# ESP32.net
KiCad netlist of a schematic drawn in Altium Designer
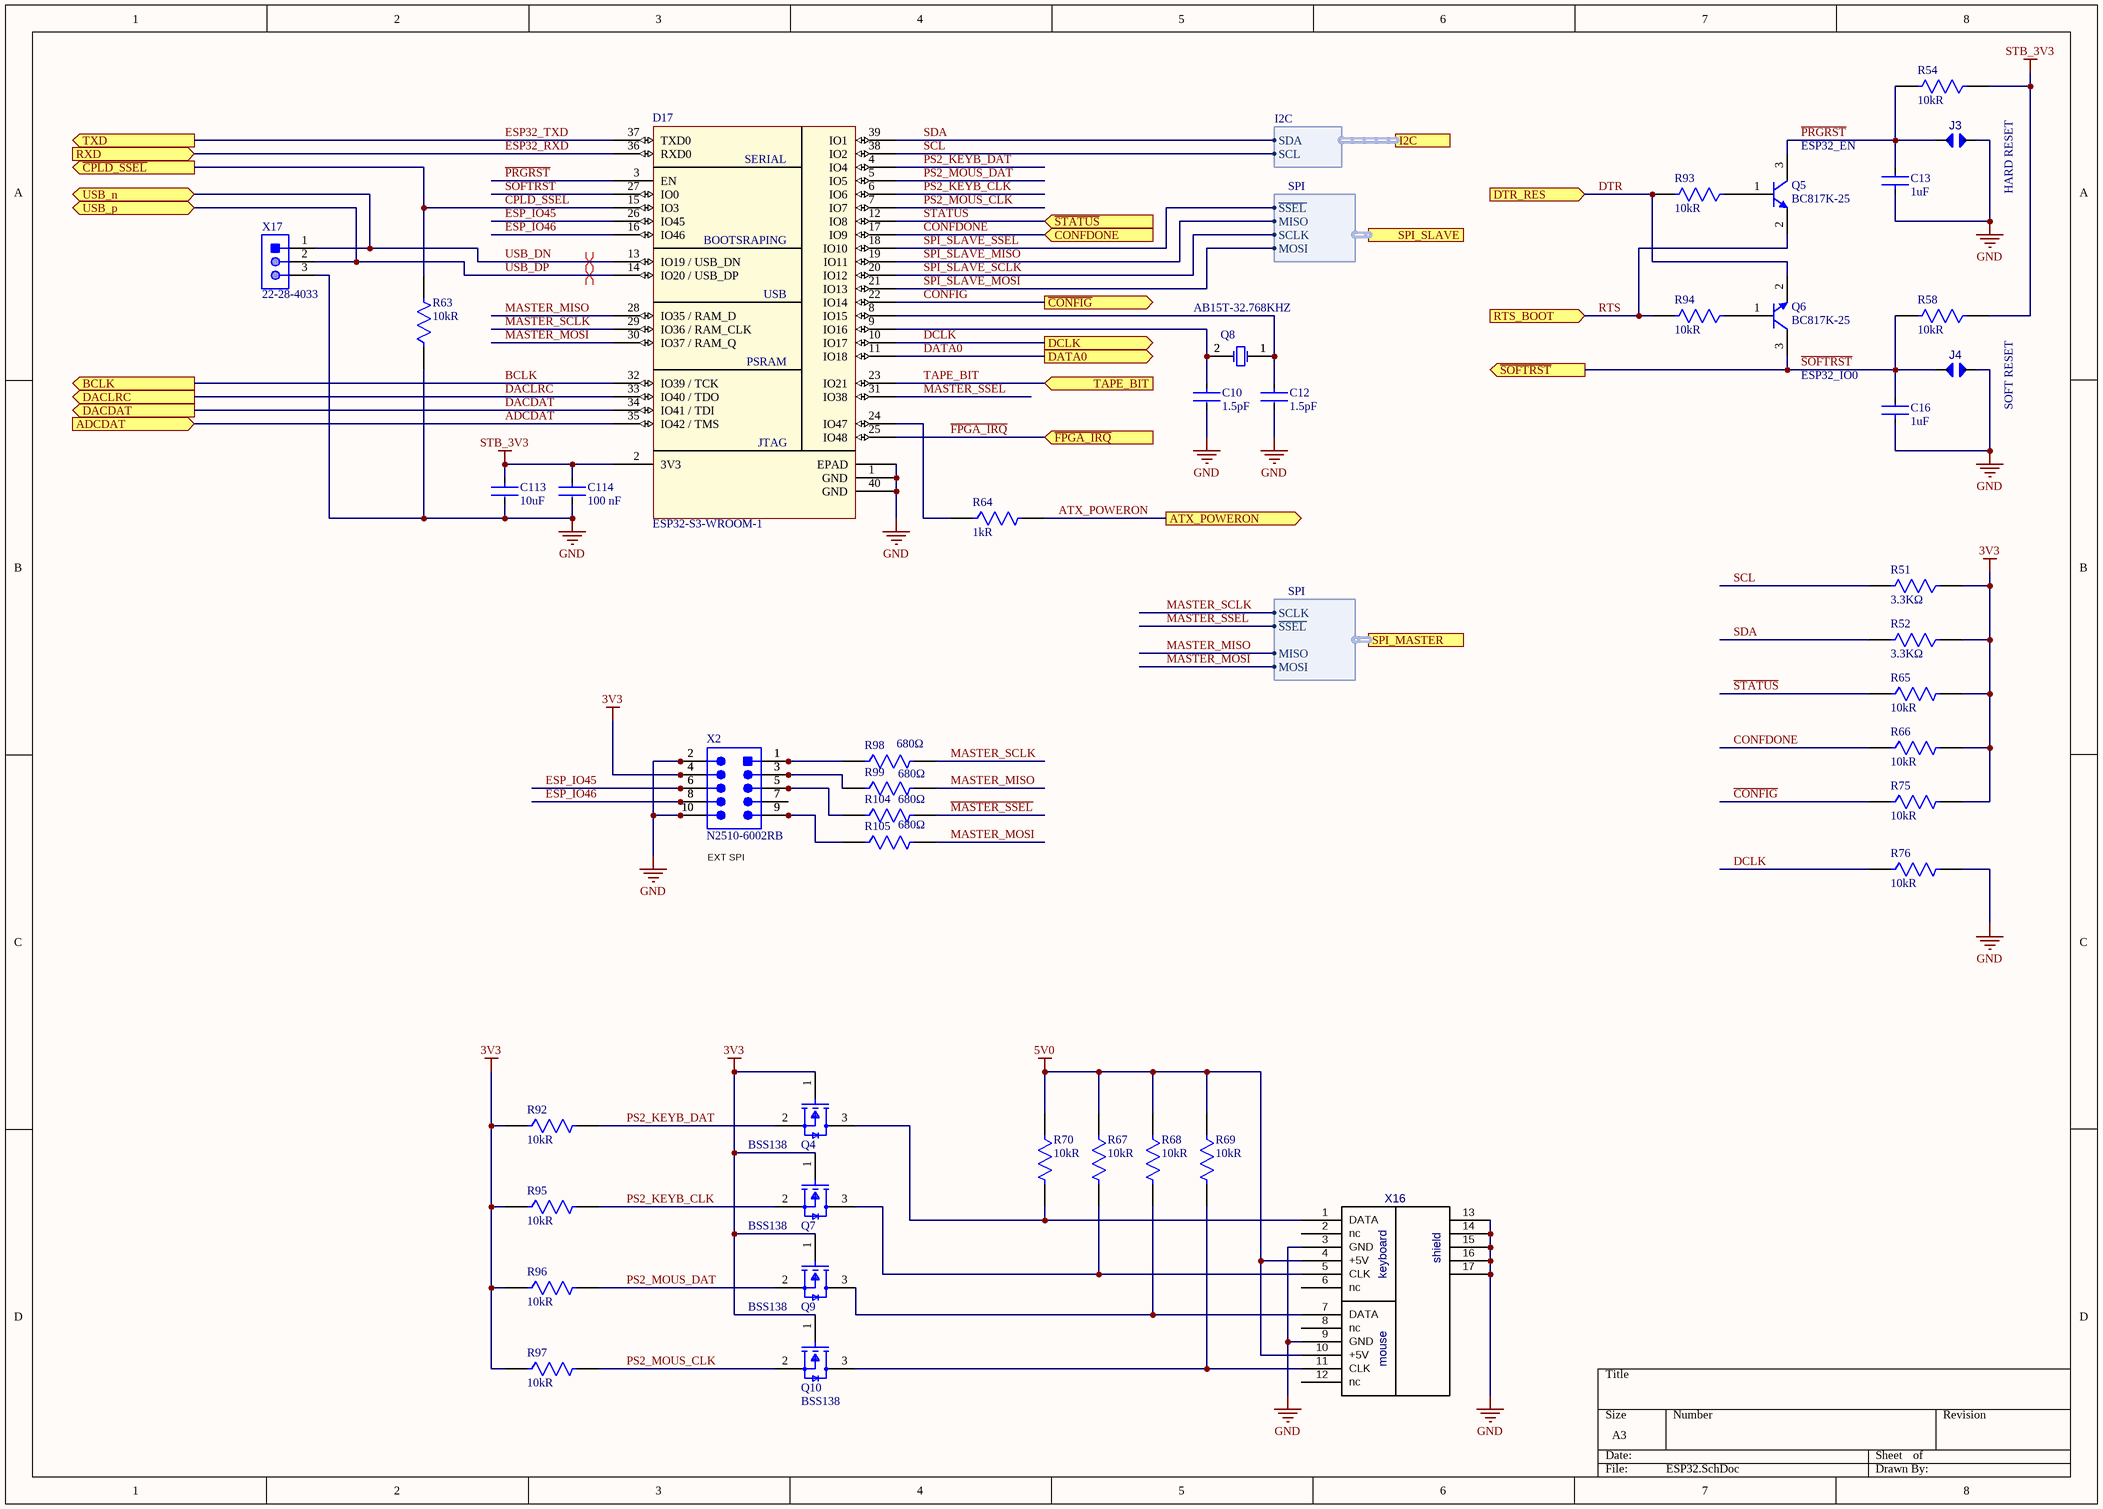
[diagram p0: ESP32.SchDoc]

(export (version "E")
  (design (tool "Eeschema 10.0.6"))
  (components
    (comp (ref "C10")
      (value "CL21C1R5CBANNNC")
      (footprint "FP-CL21-IPC_A")
      (description "CL21 Series 0805 1.5pF 50V ±0.25pF Tolerance C0G Multilayer Ceramic Chip Capacitor")
      (fields (field (name "CAPACITANCE") "1.5pF") (field (name "MANUFACTURER") "Samsung"))
      (libsource (lib "SchLib") (part "CMP-13271-001925-1"))
    )
    (comp (ref "C12")
      (value "CL21C1R5CBANNNC")
      (footprint "FP-CL21-IPC_A")
      (description "CL21 Series 0805 1.5pF 50V ±0.25pF Tolerance C0G Multilayer Ceramic Chip Capacitor")
      (fields (field (name "CAPACITANCE") "1.5pF") (field (name "MANUFACTURER") "Samsung"))
      (libsource (lib "SchLib") (part "CMP-13271-001925-1"))
    )
    (comp (ref "C13")
      (value "GCM21BR71E105KA56L")
      (footprint "FP-GCM21B-0_15-IPC_A")
      (description "Ceramic Capacitor for Automotive 1uF ±10% 25VDC X7R 0805 Embossed T/R")
      (fields (field (name "CAPACITANCE") "1uF") (field (name "MANUFACTURER") "Murata"))
      (libsource (lib "SchLib") (part "CMP-2007-03346-2"))
    )
    (comp (ref "C16")
      (value "GCM21BR71E105KA56L")
      (footprint "FP-GCM21B-0_15-IPC_A")
      (description "Ceramic Capacitor for Automotive 1uF ±10% 25VDC X7R 0805 Embossed T/R")
      (fields (field (name "CAPACITANCE") "1uF") (field (name "MANUFACTURER") "Murata"))
      (libsource (lib "SchLib") (part "CMP-2007-03346-2"))
    )
    (comp (ref "C113")
      (value "C0805C106K8PACTU")
      (footprint "FP-C0805C-DG-IPC_A")
      (description "CAP CER 10UF 10V X5R 0805")
      (fields (field (name "MANUFACTURER") "KEMET") (field (name "CAPACITANCE") "10uF"))
      (libsource (lib "SchLib") (part "CMP-2007-03243-2"))
    )
    (comp (ref "C114")
      (value "CC0805KRX7R9BB104")
      (footprint "FP-CC0805-0_85-IPC_A")
      (description "CAP CER 0.1UF 50V X7R 0805")
      (fields (field (name "MANUFACTURER") "Yageo") (field (name "CAPACITANCE") "100 nF"))
      (libsource (lib "SchLib") (part "CMP-2100-03606-3"))
    )
    (comp (ref "D17")
      (value "ESP32-S3-WROOM-1")
      (footprint "ESP32S3WROOM1")
      (libsource (lib "SchLib") (part "ESP32-S3-WROOM-1"))
    )
    (comp (ref "J3")
      (value "JUMPER")
      (footprint "JUMPER_JUMPER(Primary)")
      (description "HLT->~IP")
      (libsource (lib "SchLib") (part "JUMPER"))
    )
    (comp (ref "J4")
      (value "JUMPER")
      (footprint "JUMPER_JUMPER(Primary)")
      (description "HLT->~IP")
      (libsource (lib "SchLib") (part "JUMPER"))
    )
    (comp (ref "Q4")
      (value "BSS138")
      (footprint "FP-318-08-IPC_B")
      (description "MOSFET N-CH 50V 220MA SOT-23")
      (fields (field (name "MANUFACTURER") "ON Semiconductor / Fairchild"))
      (libsource (lib "SchLib") (part "CMP-07173-000101-1"))
    )
    (comp (ref "Q5")
      (value "BC817K-25")
      (footprint "INF-SOT23_N")
      (description "NPN Silicon AF Transistor, 45 V VCEO, 500 mA IC, SOT23, Reel, Green")
      (fields (field (name "MANUFACTURER") "Infineon"))
      (libsource (lib "SchLib") (part "CMP-1177-00027-1"))
    )
    (comp (ref "Q6")
      (value "BC817K-25")
      (footprint "INF-SOT23_N")
      (description "NPN Silicon AF Transistor, 45 V VCEO, 500 mA IC, SOT23, Reel, Green")
      (fields (field (name "MANUFACTURER") "Infineon"))
      (libsource (lib "SchLib") (part "CMP-1177-00027-1"))
    )
    (comp (ref "Q7")
      (value "BSS138")
      (footprint "FP-318-08-IPC_B")
      (description "MOSFET N-CH 50V 220MA SOT-23")
      (fields (field (name "MANUFACTURER") "ON Semiconductor / Fairchild"))
      (libsource (lib "SchLib") (part "CMP-07173-000101-1"))
    )
    (comp (ref "Q8")
      (value "AB15T-32.768KHZ")
      (footprint "ABRA-AB15T-2_V")
      (fields (field (name "MANUFACTURER") "Abracon"))
      (libsource (lib "SchLib") (part "CMP-1326-00001-1"))
    )
    (comp (ref "Q9")
      (value "BSS138")
      (footprint "FP-318-08-IPC_B")
      (description "MOSFET N-CH 50V 220MA SOT-23")
      (fields (field (name "MANUFACTURER") "ON Semiconductor / Fairchild"))
      (libsource (lib "SchLib") (part "CMP-07173-000101-1"))
    )
    (comp (ref "Q10")
      (value "BSS138")
      (footprint "FP-318-08-IPC_B")
      (description "MOSFET N-CH 50V 220MA SOT-23")
      (fields (field (name "MANUFACTURER") "ON Semiconductor / Fairchild"))
      (libsource (lib "SchLib") (part "CMP-07173-000101-1"))
    )
    (comp (ref "R51")
      (value "RT0805FRE073K3L")
      (footprint "FP-RT0805-IPC_A")
      (description "RES SMD 3.3K OHM 1% 1/8W 0805")
      (fields (field (name "MANUFACTURER") "Yageo") (field (name "RESISTANCE") "3.3KΩ"))
      (libsource (lib "SchLib") (part "CMP-03412-025935-1"))
    )
    (comp (ref "R52")
      (value "RT0805FRE073K3L")
      (footprint "FP-RT0805-IPC_A")
      (description "RES SMD 3.3K OHM 1% 1/8W 0805")
      (fields (field (name "MANUFACTURER") "Yageo") (field (name "RESISTANCE") "3.3KΩ"))
      (libsource (lib "SchLib") (part "CMP-03412-025935-1"))
    )
    (comp (ref "R54")
      (value "CR0805-JW-103ELF")
      (footprint "FP-CR0805-IPC_A")
      (description "Thick Film Chip Resistors 0805 10kΩ 0.125W 5% 200ppm/°C")
      (fields (field (name "RESISTANCE") "10kR") (field (name "MANUFACTURER") "Bourns"))
      (libsource (lib "SchLib") (part "CMP-07231-003873-1"))
    )
    (comp (ref "R58")
      (value "CR0805-JW-103ELF")
      (footprint "FP-CR0805-IPC_A")
      (description "Thick Film Chip Resistors 0805 10kΩ 0.125W 5% 200ppm/°C")
      (fields (field (name "RESISTANCE") "10kR") (field (name "MANUFACTURER") "Bourns"))
      (libsource (lib "SchLib") (part "CMP-07231-003873-1"))
    )
    (comp (ref "R63")
      (value "CR0805-JW-103ELF")
      (footprint "FP-CR0805-IPC_A")
      (description "Thick Film Chip Resistors 0805 10kΩ 0.125W 5% 200ppm/°C")
      (fields (field (name "RESISTANCE") "10kR") (field (name "MANUFACTURER") "Bourns"))
      (libsource (lib "SchLib") (part "CMP-07231-003873-1"))
    )
    (comp (ref "R64")
      (value "MCR10ERTJ102")
      (footprint "FP-MCR10-IPC_A")
      (description "Thick Film Chip Resistor, 0805, 1kΩ, 5%, 200ppm/°C, 0.125W, 150V")
      (fields (field (name "RESISTANCE") "1kR") (field (name "MANUFACTURER") "Rohm"))
      (libsource (lib "SchLib") (part "CMP-08839-004390-1"))
    )
    (comp (ref "R65")
      (value "CR0805-JW-103ELF")
      (footprint "FP-CR0805-IPC_A")
      (description "Thick Film Chip Resistors 0805 10kΩ 0.125W 5% 200ppm/°C")
      (fields (field (name "RESISTANCE") "10kR") (field (name "MANUFACTURER") "Bourns"))
      (libsource (lib "SchLib") (part "CMP-07231-003873-1"))
    )
    (comp (ref "R66")
      (value "CR0805-JW-103ELF")
      (footprint "FP-CR0805-IPC_A")
      (description "Thick Film Chip Resistors 0805 10kΩ 0.125W 5% 200ppm/°C")
      (fields (field (name "RESISTANCE") "10kR") (field (name "MANUFACTURER") "Bourns"))
      (libsource (lib "SchLib") (part "CMP-07231-003873-1"))
    )
    (comp (ref "R67")
      (value "CR0805-JW-103ELF")
      (footprint "FP-CR0805-IPC_A")
      (description "Thick Film Chip Resistors 0805 10kΩ 0.125W 5% 200ppm/°C")
      (fields (field (name "RESISTANCE") "10kR") (field (name "MANUFACTURER") "Bourns"))
      (libsource (lib "SchLib") (part "CMP-07231-003873-1"))
    )
    (comp (ref "R68")
      (value "CR0805-JW-103ELF")
      (footprint "FP-CR0805-IPC_A")
      (description "Thick Film Chip Resistors 0805 10kΩ 0.125W 5% 200ppm/°C")
      (fields (field (name "RESISTANCE") "10kR") (field (name "MANUFACTURER") "Bourns"))
      (libsource (lib "SchLib") (part "CMP-07231-003873-1"))
    )
    (comp (ref "R69")
      (value "CR0805-JW-103ELF")
      (footprint "FP-CR0805-IPC_A")
      (description "Thick Film Chip Resistors 0805 10kΩ 0.125W 5% 200ppm/°C")
      (fields (field (name "RESISTANCE") "10kR") (field (name "MANUFACTURER") "Bourns"))
      (libsource (lib "SchLib") (part "CMP-07231-003873-1"))
    )
    (comp (ref "R70")
      (value "CR0805-JW-103ELF")
      (footprint "FP-CR0805-IPC_A")
      (description "Thick Film Chip Resistors 0805 10kΩ 0.125W 5% 200ppm/°C")
      (fields (field (name "RESISTANCE") "10kR") (field (name "MANUFACTURER") "Bourns"))
      (libsource (lib "SchLib") (part "CMP-07231-003873-1"))
    )
    (comp (ref "R75")
      (value "CR0805-JW-103ELF")
      (footprint "FP-CR0805-IPC_A")
      (description "Thick Film Chip Resistors 0805 10kΩ 0.125W 5% 200ppm/°C")
      (fields (field (name "RESISTANCE") "10kR") (field (name "MANUFACTURER") "Bourns"))
      (libsource (lib "SchLib") (part "CMP-07231-003873-1"))
    )
    (comp (ref "R76")
      (value "CR0805-JW-103ELF")
      (footprint "FP-CR0805-IPC_A")
      (description "Thick Film Chip Resistors 0805 10kΩ 0.125W 5% 200ppm/°C")
      (fields (field (name "RESISTANCE") "10kR") (field (name "MANUFACTURER") "Bourns"))
      (libsource (lib "SchLib") (part "CMP-07231-003873-1"))
    )
    (comp (ref "R92")
      (value "CR0805-JW-103ELF")
      (footprint "FP-CR0805-IPC_A")
      (description "Thick Film Chip Resistors 0805 10kΩ 0.125W 5% 200ppm/°C")
      (fields (field (name "RESISTANCE") "10kR") (field (name "MANUFACTURER") "Bourns"))
      (libsource (lib "SchLib") (part "CMP-07231-003873-1"))
    )
    (comp (ref "R93")
      (value "CR0805-JW-103ELF")
      (footprint "FP-CR0805-IPC_A")
      (description "Thick Film Chip Resistors 0805 10kΩ 0.125W 5% 200ppm/°C")
      (fields (field (name "RESISTANCE") "10kR") (field (name "MANUFACTURER") "Bourns"))
      (libsource (lib "SchLib") (part "CMP-07231-003873-1"))
    )
    (comp (ref "R94")
      (value "CR0805-JW-103ELF")
      (footprint "FP-CR0805-IPC_A")
      (description "Thick Film Chip Resistors 0805 10kΩ 0.125W 5% 200ppm/°C")
      (fields (field (name "RESISTANCE") "10kR") (field (name "MANUFACTURER") "Bourns"))
      (libsource (lib "SchLib") (part "CMP-07231-003873-1"))
    )
    (comp (ref "R95")
      (value "CR0805-JW-103ELF")
      (footprint "FP-CR0805-IPC_A")
      (description "Thick Film Chip Resistors 0805 10kΩ 0.125W 5% 200ppm/°C")
      (fields (field (name "RESISTANCE") "10kR") (field (name "MANUFACTURER") "Bourns"))
      (libsource (lib "SchLib") (part "CMP-07231-003873-1"))
    )
    (comp (ref "R96")
      (value "CR0805-JW-103ELF")
      (footprint "FP-CR0805-IPC_A")
      (description "Thick Film Chip Resistors 0805 10kΩ 0.125W 5% 200ppm/°C")
      (fields (field (name "RESISTANCE") "10kR") (field (name "MANUFACTURER") "Bourns"))
      (libsource (lib "SchLib") (part "CMP-07231-003873-1"))
    )
    (comp (ref "R97")
      (value "CR0805-JW-103ELF")
      (footprint "FP-CR0805-IPC_A")
      (description "Thick Film Chip Resistors 0805 10kΩ 0.125W 5% 200ppm/°C")
      (fields (field (name "RESISTANCE") "10kR") (field (name "MANUFACTURER") "Bourns"))
      (libsource (lib "SchLib") (part "CMP-07231-003873-1"))
    )
    (comp (ref "R98")
      (value "680Ω")
      (footprint "FP-RT0805-IPC_A")
      (description "RES SMD 680 OHM 1% 1/8W 0805")
      (fields
        (field (name "MANUFACTURER") "Yageo")
        (field (name "MANUFACTURER PART NUMBER") "RT0805FRE07680RL")
      )
      (libsource (lib "SchLib") (part "CMP-03412-000082-1"))
    )
    (comp (ref "R99")
      (value "680Ω")
      (footprint "FP-RT0805-IPC_A")
      (description "RES SMD 680 OHM 1% 1/8W 0805")
      (fields
        (field (name "MANUFACTURER") "Yageo")
        (field (name "MANUFACTURER PART NUMBER") "RT0805FRE07680RL")
      )
      (libsource (lib "SchLib") (part "CMP-03412-000082-1"))
    )
    (comp (ref "R104")
      (value "680Ω")
      (footprint "FP-RT0805-IPC_A")
      (description "RES SMD 680 OHM 1% 1/8W 0805")
      (fields
        (field (name "MANUFACTURER") "Yageo")
        (field (name "MANUFACTURER PART NUMBER") "RT0805FRE07680RL")
      )
      (libsource (lib "SchLib") (part "CMP-03412-000082-1"))
    )
    (comp (ref "R105")
      (value "680Ω")
      (footprint "FP-RT0805-IPC_A")
      (description "RES SMD 680 OHM 1% 1/8W 0805")
      (fields
        (field (name "MANUFACTURER") "Yageo")
        (field (name "MANUFACTURER PART NUMBER") "RT0805FRE07680RL")
      )
      (libsource (lib "SchLib") (part "CMP-03412-000082-1"))
    )
    (comp (ref "X2")
      (value "N2510-6002RB")
      (footprint "3M-N2510-6002-10_V")
      (fields (field (name "PARTNUMBER") "N2510") (field (name "MANUFACTURER") "3M"))
      (libsource (lib "SchLib") (part "CMP-2000-06794-1"))
    )
    (comp (ref "X16")
      (value "KEYB-MOUSE")
      (footprint "MDD-6FR")
      (libsource (lib "SchLib") (part "KEYB-MOUSE"))
    )
    (comp (ref "X17")
      (value "22-28-4033")
      (footprint "MOLX-22-28-4033_V")
      (description "Male Header, Pitch 2.54 mm, 1 x 3 Position, Height 8.38 mm, Tail Length 3.18 mm, RoHS, Bulk")
      (fields (field (name "MANUFACTURER") "Molex"))
      (libsource (lib "SchLib") (part "CMP-1676-00001-5"))
    )
  )
  (nets
    (net (code "3") (name "/ADCDAT") (class "Default")
      (node (ref "D17") (pin "35") (pinfunction "IO42_/_TMS_35") (pintype "bidirectional"))
    )
    (net (code "4") (name "/ATX_POWERON") (class "Default")
      (node (ref "R64") (pin "2") (pinfunction "2_2") (pintype "passive"))
    )
    (net (code "5") (name "/BCLK") (class "Default")
      (node (ref "D17") (pin "32") (pinfunction "IO39_/_TCK_32") (pintype "bidirectional"))
    )
    (net (code "6") (name "/CONFDONE") (class "Default")
      (node (ref "D17") (pin "17") (pinfunction "IO9_17") (pintype "bidirectional"))
      (node (ref "R66") (pin "1") (pinfunction "1_1") (pintype "passive"))
    )
    (net (code "7") (name "/DACDAT") (class "Default")
      (node (ref "D17") (pin "34") (pinfunction "IO41_/_TDI_34") (pintype "bidirectional"))
    )
    (net (code "8") (name "/DACLRC") (class "Default")
      (node (ref "D17") (pin "33") (pinfunction "IO40_/_TDO_33") (pintype "bidirectional"))
    )
    (net (code "9") (name "/DATA0") (class "Default")
      (node (ref "D17") (pin "11") (pinfunction "IO18_11") (pintype "bidirectional"))
    )
    (net (code "10") (name "/DCLK") (class "Default")
      (node (ref "D17") (pin "10") (pinfunction "IO17_10") (pintype "bidirectional"))
      (node (ref "R76") (pin "1") (pinfunction "1_1") (pintype "passive"))
    )
    (net (code "11") (name "/DTR") (class "Default")
      (node (ref "Q6") (pin "2") (pinfunction "E_2") (pintype "passive"))
      (node (ref "R93") (pin "2") (pinfunction "2_2") (pintype "passive"))
    )
    (net (code "12") (name "/ESP32_RXD") (class "Default")
      (node (ref "D17") (pin "36") (pinfunction "RXD0_36") (pintype "bidirectional"))
    )
    (net (code "13") (name "/ESP32_TXD") (class "Default")
      (node (ref "D17") (pin "37") (pinfunction "TXD0_37") (pintype "bidirectional"))
    )
    (net (code "14") (name "/ESP_IO45") (class "Default")
      (node (ref "D17") (pin "26") (pinfunction "IO45_26") (pintype "bidirectional"))
      (node (ref "X2") (pin "6") (pinfunction "6_6") (pintype "passive"))
    )
    (net (code "15") (name "/ESP_IO46") (class "Default")
      (node (ref "D17") (pin "16") (pinfunction "IO46_16") (pintype "bidirectional"))
      (node (ref "X2") (pin "8") (pinfunction "8_8") (pintype "passive"))
    )
    (net (code "16") (name "/MASTER_MISO") (class "Default")
      (node (ref "D17") (pin "28") (pinfunction "IO35_/_RAM_D_28") (pintype "bidirectional"))
      (node (ref "R99") (pin "2") (pinfunction "2_2") (pintype "passive"))
    )
    (net (code "17") (name "/MASTER_MOSI") (class "Default")
      (node (ref "D17") (pin "30") (pinfunction "IO37_/_RAM_Q_30") (pintype "bidirectional"))
      (node (ref "R105") (pin "2") (pinfunction "2_2") (pintype "passive"))
    )
    (net (code "18") (name "/MASTER_SCLK") (class "Default")
      (node (ref "D17") (pin "29") (pinfunction "IO36_/_RAM_CLK_29") (pintype "bidirectional"))
      (node (ref "R98") (pin "2") (pinfunction "2_2") (pintype "passive"))
    )
    (net (code "19") (name "/PS2_KEYB_CLK") (class "Default")
      (node (ref "D17") (pin "6") (pinfunction "IO6_6") (pintype "bidirectional"))
      (node (ref "Q7") (pin "2") (pinfunction "S_2") (pintype "passive"))
      (node (ref "R95") (pin "2") (pinfunction "2_2") (pintype "passive"))
    )
    (net (code "20") (name "/PS2_KEYB_DAT") (class "Default")
      (node (ref "D17") (pin "4") (pinfunction "IO4_4") (pintype "bidirectional"))
      (node (ref "Q4") (pin "2") (pinfunction "S_2") (pintype "passive"))
      (node (ref "R92") (pin "2") (pinfunction "2_2") (pintype "passive"))
    )
    (net (code "21") (name "/PS2_MOUS_CLK") (class "Default")
      (node (ref "D17") (pin "7") (pinfunction "IO7_7") (pintype "bidirectional"))
      (node (ref "Q10") (pin "2") (pinfunction "S_2") (pintype "passive"))
      (node (ref "R97") (pin "2") (pinfunction "2_2") (pintype "passive"))
    )
    (net (code "22") (name "/PS2_MOUS_DAT") (class "Default")
      (node (ref "D17") (pin "5") (pinfunction "IO5_5") (pintype "bidirectional"))
      (node (ref "Q9") (pin "2") (pinfunction "S_2") (pintype "passive"))
      (node (ref "R96") (pin "2") (pinfunction "2_2") (pintype "passive"))
    )
    (net (code "23") (name "/RTS") (class "Default")
      (node (ref "Q5") (pin "2") (pinfunction "E_2") (pintype "passive"))
      (node (ref "R94") (pin "2") (pinfunction "2_2") (pintype "passive"))
    )
    (net (code "24") (name "/SCL") (class "Default")
      (node (ref "D17") (pin "38") (pinfunction "IO2_38") (pintype "bidirectional"))
      (node (ref "R51") (pin "2") (pinfunction "2_2") (pintype "passive"))
    )
    (net (code "25") (name "/SDA") (class "Default")
      (node (ref "D17") (pin "39") (pinfunction "IO1_39") (pintype "bidirectional"))
      (node (ref "R52") (pin "2") (pinfunction "2_2") (pintype "passive"))
    )
    (net (code "26") (name "/SPI_SLAVE_MISO") (class "Default")
      (node (ref "D17") (pin "19") (pinfunction "IO11_19") (pintype "bidirectional"))
    )
    (net (code "27") (name "/SPI_SLAVE_MOSI") (class "Default")
      (node (ref "D17") (pin "21") (pinfunction "IO13_21") (pintype "bidirectional"))
    )
    (net (code "28") (name "/SPI_SLAVE_SCLK") (class "Default")
      (node (ref "D17") (pin "20") (pinfunction "IO12_20") (pintype "bidirectional"))
    )
    (net (code "29") (name "/TAPE_BIT") (class "Default")
      (node (ref "D17") (pin "23") (pinfunction "IO21_23") (pintype "bidirectional"))
    )
    (net (code "30") (name "/USB_DN") (class "Default")
      (node (ref "D17") (pin "13") (pinfunction "IO19_/_USB_DN_13") (pintype "bidirectional"))
      (node (ref "X17") (pin "1") (pinfunction "1_1") (pintype "passive"))
    )
    (net (code "31") (name "/USB_DP") (class "Default")
      (node (ref "D17") (pin "14") (pinfunction "IO20_/_USB_DP_14") (pintype "bidirectional"))
      (node (ref "X17") (pin "2") (pinfunction "2_2") (pintype "passive"))
    )
    (net (code "34") (name "/~{CONFIG}") (class "Default")
      (node (ref "D17") (pin "22") (pinfunction "IO14_22") (pintype "bidirectional"))
      (node (ref "R75") (pin "1") (pinfunction "1_1") (pintype "passive"))
    )
    (net (code "35") (name "/~{CPLD_SSEL}") (class "Default")
      (node (ref "D17") (pin "15") (pinfunction "IO3_15") (pintype "bidirectional"))
      (node (ref "R63") (pin "2") (pinfunction "2_2") (pintype "passive"))
    )
    (net (code "36") (name "/~{FPGA_IRQ}") (class "Default")
      (node (ref "D17") (pin "25") (pinfunction "IO48_25") (pintype "bidirectional"))
    )
    (net (code "37") (name "/~{MASTER_SSEL}") (class "Default")
      (node (ref "D17") (pin "31") (pinfunction "IO38_31") (pintype "bidirectional"))
      (node (ref "R104") (pin "2") (pinfunction "2_2") (pintype "passive"))
    )
    (net (code "38") (name "/~{PRGRST}") (class "Default")
      (node (ref "C13") (pin "2") (pinfunction "2_2") (pintype "passive"))
      (node (ref "D17") (pin "3") (pinfunction "EN_3") (pintype "power_in"))
      (node (ref "J3") (pin "0") (pinfunction "1_0") (pintype "passive"))
      (node (ref "Q5") (pin "3") (pinfunction "C_3") (pintype "passive"))
      (node (ref "R54") (pin "2") (pinfunction "2_2") (pintype "passive"))
    )
    (net (code "39") (name "/~{SOFTRST}") (class "Default")
      (node (ref "C16") (pin "2") (pinfunction "2_2") (pintype "passive"))
      (node (ref "D17") (pin "27") (pinfunction "IO0_27") (pintype "bidirectional"))
      (node (ref "J4") (pin "0") (pinfunction "1_0") (pintype "passive"))
      (node (ref "Q6") (pin "3") (pinfunction "C_3") (pintype "passive"))
      (node (ref "R58") (pin "2") (pinfunction "2_2") (pintype "passive"))
    )
    (net (code "40") (name "/~{SPI_SLAVE_SSEL}") (class "Default")
      (node (ref "D17") (pin "18") (pinfunction "IO10_18") (pintype "bidirectional"))
    )
    (net (code "41") (name "/~{STATUS}") (class "Default")
      (node (ref "D17") (pin "12") (pinfunction "IO8_12") (pintype "bidirectional"))
      (node (ref "R65") (pin "1") (pinfunction "1_1") (pintype "passive"))
    )
    (net (code "42") (name "3V3") (class "Default")
      (node (ref "Q10") (pin "1") (pinfunction "G_1") (pintype "passive"))
      (node (ref "Q4") (pin "1") (pinfunction "G_1") (pintype "passive"))
      (node (ref "Q7") (pin "1") (pinfunction "G_1") (pintype "passive"))
      (node (ref "Q9") (pin "1") (pinfunction "G_1") (pintype "passive"))
      (node (ref "R51") (pin "1") (pinfunction "1_1") (pintype "passive"))
      (node (ref "R52") (pin "1") (pinfunction "1_1") (pintype "passive"))
      (node (ref "R65") (pin "2") (pinfunction "2_2") (pintype "passive"))
      (node (ref "R66") (pin "2") (pinfunction "2_2") (pintype "passive"))
      (node (ref "R75") (pin "2") (pinfunction "2_2") (pintype "passive"))
      (node (ref "R92") (pin "1") (pinfunction "1_1") (pintype "passive"))
      (node (ref "R95") (pin "1") (pinfunction "1_1") (pintype "passive"))
      (node (ref "R96") (pin "1") (pinfunction "1_1") (pintype "passive"))
      (node (ref "R97") (pin "1") (pinfunction "1_1") (pintype "passive"))
      (node (ref "X2") (pin "4") (pinfunction "4_4") (pintype "passive"))
    )
    (net (code "43") (name "5V0") (class "Default")
      (node (ref "R67") (pin "1") (pinfunction "1_1") (pintype "passive"))
      (node (ref "R68") (pin "1") (pinfunction "1_1") (pintype "passive"))
      (node (ref "R69") (pin "1") (pinfunction "1_1") (pintype "passive"))
      (node (ref "R70") (pin "1") (pinfunction "1_1") (pintype "passive"))
      (node (ref "X16") (pin "10") (pinfunction "+5V_10") (pintype "passive"))
      (node (ref "X16") (pin "4") (pinfunction "+5V_4") (pintype "passive"))
    )
    (net (code "44") (name "GND") (class "Default")
      (node (ref "C10") (pin "2") (pinfunction "2_2") (pintype "passive"))
      (node (ref "C113") (pin "2") (pinfunction "2_2") (pintype "passive"))
      (node (ref "C114") (pin "2") (pinfunction "2_2") (pintype "passive"))
      (node (ref "C12") (pin "2") (pinfunction "2_2") (pintype "passive"))
      (node (ref "C13") (pin "1") (pinfunction "1_1") (pintype "passive"))
      (node (ref "C16") (pin "1") (pinfunction "1_1") (pintype "passive"))
      (node (ref "D17") (pin "1") (pinfunction "GND_1") (pintype "power_in"))
      (node (ref "D17") (pin "40") (pinfunction "GND_40") (pintype "power_in"))
      (node (ref "D17") (pin "EPAD") (pinfunction "EPAD_EPAD") (pintype "power_in"))
      (node (ref "J3") (pin "1") (pinfunction "2_1") (pintype "passive"))
      (node (ref "J4") (pin "1") (pinfunction "2_1") (pintype "passive"))
      (node (ref "R63") (pin "1") (pinfunction "1_1") (pintype "passive"))
      (node (ref "R76") (pin "2") (pinfunction "2_2") (pintype "passive"))
      (node (ref "X16") (pin "13") (pinfunction "shield_13") (pintype "passive"))
      (node (ref "X16") (pin "14") (pinfunction "shield_14") (pintype "passive"))
      (node (ref "X16") (pin "15") (pinfunction "shield_15") (pintype "passive"))
      (node (ref "X16") (pin "16") (pinfunction "shield_16") (pintype "passive"))
      (node (ref "X16") (pin "17") (pinfunction "shield_17") (pintype "passive"))
      (node (ref "X16") (pin "3") (pinfunction "GND_3") (pintype "passive"))
      (node (ref "X16") (pin "9") (pinfunction "GND_9") (pintype "passive"))
      (node (ref "X17") (pin "3") (pinfunction "3_3") (pintype "passive"))
      (node (ref "X2") (pin "10") (pinfunction "10_10") (pintype "passive"))
      (node (ref "X2") (pin "2") (pinfunction "2_2") (pintype "passive"))
    )
    (net (code "45") (name "Net-(D17-IO15)") (class "Default")
      (node (ref "C12") (pin "1") (pinfunction "1_1") (pintype "passive"))
      (node (ref "D17") (pin "8") (pinfunction "IO15_8") (pintype "bidirectional"))
      (node (ref "Q8") (pin "1") (pinfunction "X1_1") (pintype "passive"))
    )
    (net (code "46") (name "Net-(D17-IO16)") (class "Default")
      (node (ref "C10") (pin "1") (pinfunction "1_1") (pintype "passive"))
      (node (ref "D17") (pin "9") (pinfunction "IO16_9") (pintype "bidirectional"))
      (node (ref "Q8") (pin "2") (pinfunction "X2_2") (pintype "passive"))
    )
    (net (code "47") (name "Net-(D17-IO47)") (class "Default")
      (node (ref "D17") (pin "24") (pinfunction "IO47_24") (pintype "bidirectional"))
      (node (ref "R64") (pin "1") (pinfunction "1_1") (pintype "passive"))
    )
    (net (code "48") (name "Net-(Q4-D)") (class "Default")
      (node (ref "Q4") (pin "3") (pinfunction "D_3") (pintype "passive"))
      (node (ref "R70") (pin "2") (pinfunction "2_2") (pintype "passive"))
      (node (ref "X16") (pin "1") (pinfunction "DATA_1") (pintype "passive"))
    )
    (net (code "49") (name "Net-(Q5-B)") (class "Default")
      (node (ref "Q5") (pin "1") (pinfunction "B_1") (pintype "passive"))
      (node (ref "R93") (pin "1") (pinfunction "1_1") (pintype "passive"))
    )
    (net (code "50") (name "Net-(Q6-B)") (class "Default")
      (node (ref "Q6") (pin "1") (pinfunction "B_1") (pintype "passive"))
      (node (ref "R94") (pin "1") (pinfunction "1_1") (pintype "passive"))
    )
    (net (code "51") (name "Net-(Q7-D)") (class "Default")
      (node (ref "Q7") (pin "3") (pinfunction "D_3") (pintype "passive"))
      (node (ref "R67") (pin "2") (pinfunction "2_2") (pintype "passive"))
      (node (ref "X16") (pin "5") (pinfunction "CLK_5") (pintype "passive"))
    )
    (net (code "52") (name "Net-(Q9-D)") (class "Default")
      (node (ref "Q9") (pin "3") (pinfunction "D_3") (pintype "passive"))
      (node (ref "R68") (pin "2") (pinfunction "2_2") (pintype "passive"))
      (node (ref "X16") (pin "7") (pinfunction "DATA_7") (pintype "passive"))
    )
    (net (code "53") (name "Net-(Q10-D)") (class "Default")
      (node (ref "Q10") (pin "3") (pinfunction "D_3") (pintype "passive"))
      (node (ref "R69") (pin "2") (pinfunction "2_2") (pintype "passive"))
      (node (ref "X16") (pin "11") (pinfunction "CLK_11") (pintype "passive"))
    )
    (net (code "54") (name "Net-(R98-Pad1)") (class "Default")
      (node (ref "R98") (pin "1") (pinfunction "1_1") (pintype "passive"))
      (node (ref "X2") (pin "1") (pinfunction "1_1") (pintype "passive"))
    )
    (net (code "55") (name "Net-(R99-Pad1)") (class "Default")
      (node (ref "R99") (pin "1") (pinfunction "1_1") (pintype "passive"))
      (node (ref "X2") (pin "3") (pinfunction "3_3") (pintype "passive"))
    )
    (net (code "56") (name "Net-(R104-Pad1)") (class "Default")
      (node (ref "R104") (pin "1") (pinfunction "1_1") (pintype "passive"))
      (node (ref "X2") (pin "5") (pinfunction "5_5") (pintype "passive"))
    )
    (net (code "57") (name "Net-(R105-Pad1)") (class "Default")
      (node (ref "R105") (pin "1") (pinfunction "1_1") (pintype "passive"))
      (node (ref "X2") (pin "9") (pinfunction "9_9") (pintype "passive"))
    )
    (net (code "58") (name "Net-(X2-Pad7)") (class "Default")
      (node (ref "X2") (pin "7") (pinfunction "7_7") (pintype "passive"))
    )
    (net (code "59") (name "STB_3V3") (class "Default")
      (node (ref "C113") (pin "1") (pinfunction "1_1") (pintype "passive"))
      (node (ref "C114") (pin "1") (pinfunction "1_1") (pintype "passive"))
      (node (ref "D17") (pin "2") (pinfunction "3V3_2") (pintype "power_in"))
      (node (ref "R54") (pin "1") (pinfunction "1_1") (pintype "passive"))
      (node (ref "R58") (pin "1") (pinfunction "1_1") (pintype "passive"))
    )
    (net (code "60") (name "unconnected-(X16-nc-Pad2)") (class "Default")
      (node (ref "X16") (pin "2") (pinfunction "nc_2") (pintype "passive"))
    )
    (net (code "61") (name "unconnected-(X16-nc-Pad6)") (class "Default")
      (node (ref "X16") (pin "6") (pinfunction "nc_6") (pintype "passive"))
    )
    (net (code "62") (name "unconnected-(X16-nc-Pad8)") (class "Default")
      (node (ref "X16") (pin "8") (pinfunction "nc_8") (pintype "passive"))
    )
    (net (code "63") (name "unconnected-(X16-nc-Pad12)") (class "Default")
      (node (ref "X16") (pin "12") (pinfunction "nc_12") (pintype "passive"))
    )
  )
)
